# Sheet1.net
KiCad netlist of a schematic drawn in Altium Designer
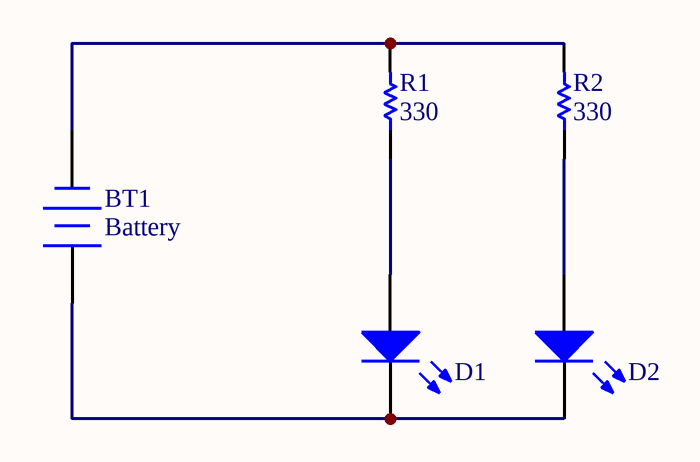
[diagram p0: Sheet1.SchDoc]

(export (version "E")
  (design (tool "Eeschema 10.0.6"))
  (components
    (comp (ref "BT1")
      (value "Battery")
      (footprint "BAT-2")
      (description "Multicell Battery")
      (fields (field (name "PUBLISHER") "Altium Limited"))
      (libsource (lib "Miscellaneous Devices") (part "Battery"))
    )
    (comp (ref "D1")
      (value "LED 3mm")
      (footprint "LED-3mm")
      (description "Typical LED")
      (fields (field (name "DESIGNER") "Seyed Mohsen Ghasemian") (field (name "PUBLISHER") "www.picpars.com"))
      (libsource (lib "PicPars.com_usefully_Library") (part "LED 3mm"))
    )
    (comp (ref "D2")
      (value "LED 3mm")
      (footprint "LED-3mm")
      (description "Typical LED")
      (fields (field (name "DESIGNER") "Seyed Mohsen Ghasemian") (field (name "PUBLISHER") "www.picpars.com"))
      (libsource (lib "PicPars.com_usefully_Library") (part "LED 3mm"))
    )
    (comp (ref "R1")
      (value "330")
      (footprint "Res50")
      (description "Resistor 0.5")
      (fields
        (field (name "Comment") "Resistor vertical")
        (field (name "PUBLISHER") "Seyed mohsen ghasemian")
      )
      (libsource (lib "PicPars.com_usefully_Library") (part "Resistor vertical"))
    )
    (comp (ref "R2")
      (value "330")
      (footprint "Res50")
      (description "Resistor 0.5")
      (fields
        (field (name "Comment") "Resistor vertical")
        (field (name "PUBLISHER") "Seyed mohsen ghasemian")
      )
      (libsource (lib "PicPars.com_usefully_Library") (part "Resistor vertical"))
    )
  )
  (nets
    (net (code "1") (name "Net-(BT1-+)") (class "Default")
      (node (ref "BT1") (pin "1") (pinfunction "+_1") (pintype "passive"))
      (node (ref "D1") (pin "2") (pinfunction "K_2") (pintype "passive"))
      (node (ref "D2") (pin "2") (pinfunction "K_2") (pintype "passive"))
    )
    (net (code "2") (name "Net-(BT1--)") (class "Default")
      (node (ref "BT1") (pin "2") (pinfunction "-_2") (pintype "passive"))
      (node (ref "R1") (pin "2") (pinfunction "2_2") (pintype "passive"))
      (node (ref "R2") (pin "2") (pinfunction "2_2") (pintype "passive"))
    )
    (net (code "3") (name "Net-(D1-A)") (class "Default")
      (node (ref "D1") (pin "1") (pinfunction "A_1") (pintype "passive"))
      (node (ref "R1") (pin "1") (pinfunction "1_1") (pintype "passive"))
    )
    (net (code "4") (name "Net-(D2-A)") (class "Default")
      (node (ref "D2") (pin "1") (pinfunction "A_1") (pintype "passive"))
      (node (ref "R2") (pin "1") (pinfunction "1_1") (pintype "passive"))
    )
  )
)
